# Smartwatch-EXTRA-AUX1.net
KiCad netlist of a schematic drawn in EAGLE
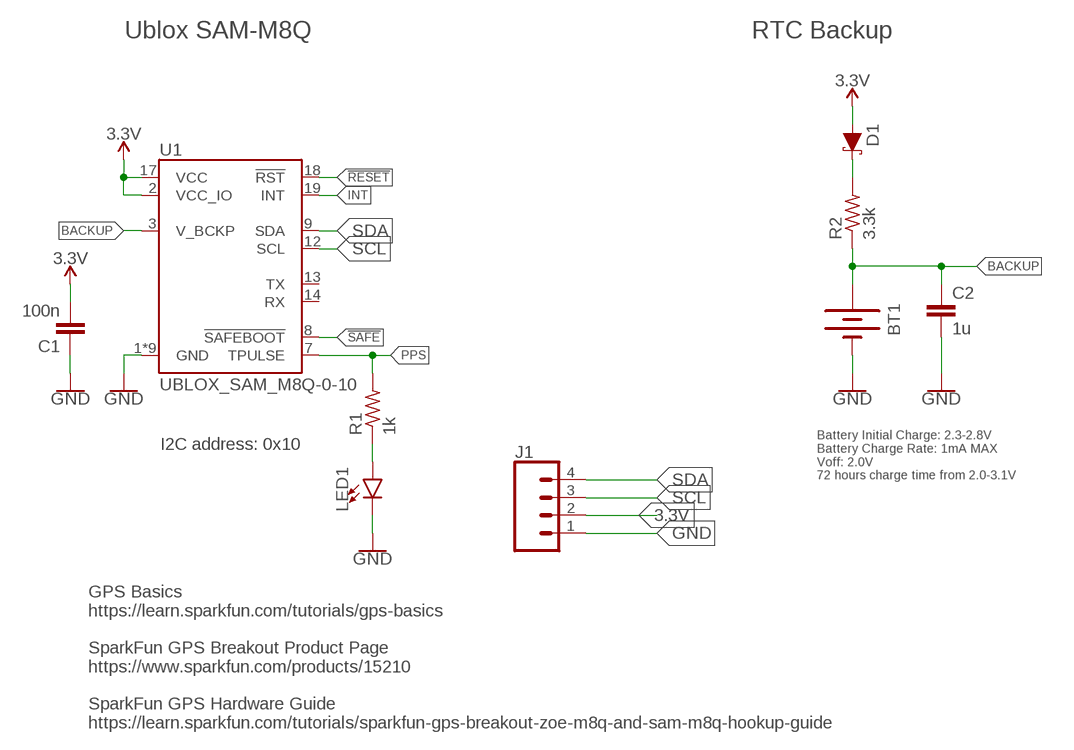
[diagram p0: schematic, sheet 1]

(export (version "E")
  (design (tool "Eeschema 10.0.6"))
  (components
    (comp (ref "BT1")
      (value "ML414H_IV01E_BATTERY")
      (footprint "eagle-import:ML414H_IV01E")
      (fields (field (name "MANUFACTURER") "Seiko Instruments"))
      (libsource (lib "eagle-import") (part "ML414H_IV01E_BATTERY"))
    )
    (comp (ref "C1")
      (value "100n")
      (footprint "eagle-import:C0603")
      (libsource (lib "eagle-import") (part "CAPACITOR0603"))
    )
    (comp (ref "C2")
      (value "1u")
      (footprint "eagle-import:C0603")
      (libsource (lib "eagle-import") (part "CAPACITOR0603"))
    )
    (comp (ref "D1")
      (value "SCHOTTKY-USC")
      (footprint "eagle-import:USC")
      (libsource (lib "eagle-import") (part "SCHOTTKY-USC"))
    )
    (comp (ref "J1")
      (value "CONN_041.27MM")
      (footprint "eagle-import:1X04_1.27MM")
      (libsource (lib "eagle-import") (part "CONN_041.27MM"))
    )
    (comp (ref "LED1")
      (value "LED0603")
      (footprint "eagle-import:LED-0603")
      (libsource (lib "eagle-import") (part "LED0603"))
    )
    (comp (ref "R1")
      (value "1k")
      (footprint "eagle-import:R0603")
      (libsource (lib "eagle-import") (part "RESISTOR0603"))
    )
    (comp (ref "R2")
      (value "3.3k")
      (footprint "eagle-import:R0603")
      (libsource (lib "eagle-import") (part "RESISTOR0603"))
    )
    (comp (ref "U1")
      (value "UBLOX_SAM_M8Q-0-10")
      (footprint "eagle-import:SAM-M8Q")
      (fields (field (name "MANUFACTURER") "U-Blox"))
      (libsource (lib "eagle-import") (part "UBLOX_SAM_M8Q-0-10"))
    )
  )
  (nets
    (net (code "1") (name "/~{RESET}") (class "Default")
      (node (ref "U1") (pin "18") (pinfunction "~{RST}_18") (pintype "bidirectional"))
    )
    (net (code "2") (name "/~{SAFE}") (class "Default")
      (node (ref "U1") (pin "8") (pinfunction "~{SAFEBOOT}_8") (pintype "bidirectional"))
    )
    (net (code "3") (name "3.3V") (class "Default")
      (node (ref "C1") (pin "2") (pinfunction "2_2") (pintype "passive"))
      (node (ref "D1") (pin "+") (pinfunction "A_+") (pintype "passive"))
      (node (ref "J1") (pin "2") (pinfunction "2_2") (pintype "passive"))
      (node (ref "U1") (pin "17") (pinfunction "VCC_17") (pintype "bidirectional"))
      (node (ref "U1") (pin "2") (pinfunction "VCC_IO_2") (pintype "bidirectional"))
    )
    (net (code "4") (name "BACKUP") (class "Default")
      (node (ref "BT1") (pin "+") (pinfunction "+_+") (pintype "power_in"))
      (node (ref "C2") (pin "1") (pinfunction "1_1") (pintype "passive"))
      (node (ref "R2") (pin "1") (pinfunction "1_1") (pintype "passive"))
      (node (ref "U1") (pin "3") (pinfunction "V_BCKP_3") (pintype "bidirectional"))
    )
    (net (code "5") (name "GND") (class "Default")
      (node (ref "BT1") (pin "-") (pinfunction "-_-") (pintype "power_in"))
      (node (ref "C1") (pin "1") (pinfunction "1_1") (pintype "passive"))
      (node (ref "C2") (pin "2") (pinfunction "2_2") (pintype "passive"))
      (node (ref "J1") (pin "1") (pinfunction "1_1") (pintype "passive"))
      (node (ref "LED1") (pin "C") (pinfunction "C_C") (pintype "passive"))
      (node (ref "U1") (pin "1") (pinfunction "GND_1") (pintype "bidirectional"))
      (node (ref "U1") (pin "10") (pinfunction "GND_10") (pintype "bidirectional"))
      (node (ref "U1") (pin "11") (pinfunction "GND_11") (pintype "bidirectional"))
      (node (ref "U1") (pin "15") (pinfunction "GND_15") (pintype "bidirectional"))
      (node (ref "U1") (pin "16") (pinfunction "GND_16") (pintype "bidirectional"))
      (node (ref "U1") (pin "20") (pinfunction "GND_20") (pintype "bidirectional"))
      (node (ref "U1") (pin "4") (pinfunction "GND_4") (pintype "bidirectional"))
      (node (ref "U1") (pin "5") (pinfunction "GND_5") (pintype "bidirectional"))
      (node (ref "U1") (pin "6") (pinfunction "GND_6") (pintype "bidirectional"))
    )
    (net (code "6") (name "INT") (class "Default")
      (node (ref "U1") (pin "19") (pinfunction "INT_19") (pintype "bidirectional"))
    )
    (net (code "7") (name "Net-(D1-C)") (class "Default")
      (node (ref "D1") (pin "-") (pinfunction "C_-") (pintype "passive"))
      (node (ref "R2") (pin "2") (pinfunction "2_2") (pintype "passive"))
    )
    (net (code "8") (name "Net-(LED1-PadA)") (class "Default")
      (node (ref "LED1") (pin "A") (pinfunction "A_A") (pintype "passive"))
      (node (ref "R1") (pin "1") (pinfunction "1_1") (pintype "passive"))
    )
    (net (code "9") (name "PPS") (class "Default")
      (node (ref "R1") (pin "2") (pinfunction "2_2") (pintype "passive"))
      (node (ref "U1") (pin "7") (pinfunction "TPULSE_7") (pintype "bidirectional"))
    )
    (net (code "10") (name "SCL") (class "Default")
      (node (ref "J1") (pin "3") (pinfunction "3_3") (pintype "passive"))
      (node (ref "U1") (pin "12") (pinfunction "SCL_12") (pintype "bidirectional"))
    )
    (net (code "11") (name "SDA") (class "Default")
      (node (ref "J1") (pin "4") (pinfunction "4_4") (pintype "passive"))
      (node (ref "U1") (pin "9") (pinfunction "SDA_9") (pintype "bidirectional"))
    )
    (net (code "12") (name "unconnected-(U1-RX-Pad14)") (class "Default")
      (node (ref "U1") (pin "14") (pinfunction "RX_14") (pintype "bidirectional"))
    )
    (net (code "13") (name "unconnected-(U1-TX-Pad13)") (class "Default")
      (node (ref "U1") (pin "13") (pinfunction "TX_13") (pintype "bidirectional"))
    )
  )
)
